# js220_fp_sba.net
KiCad netlist of a schematic drawn in EAGLE
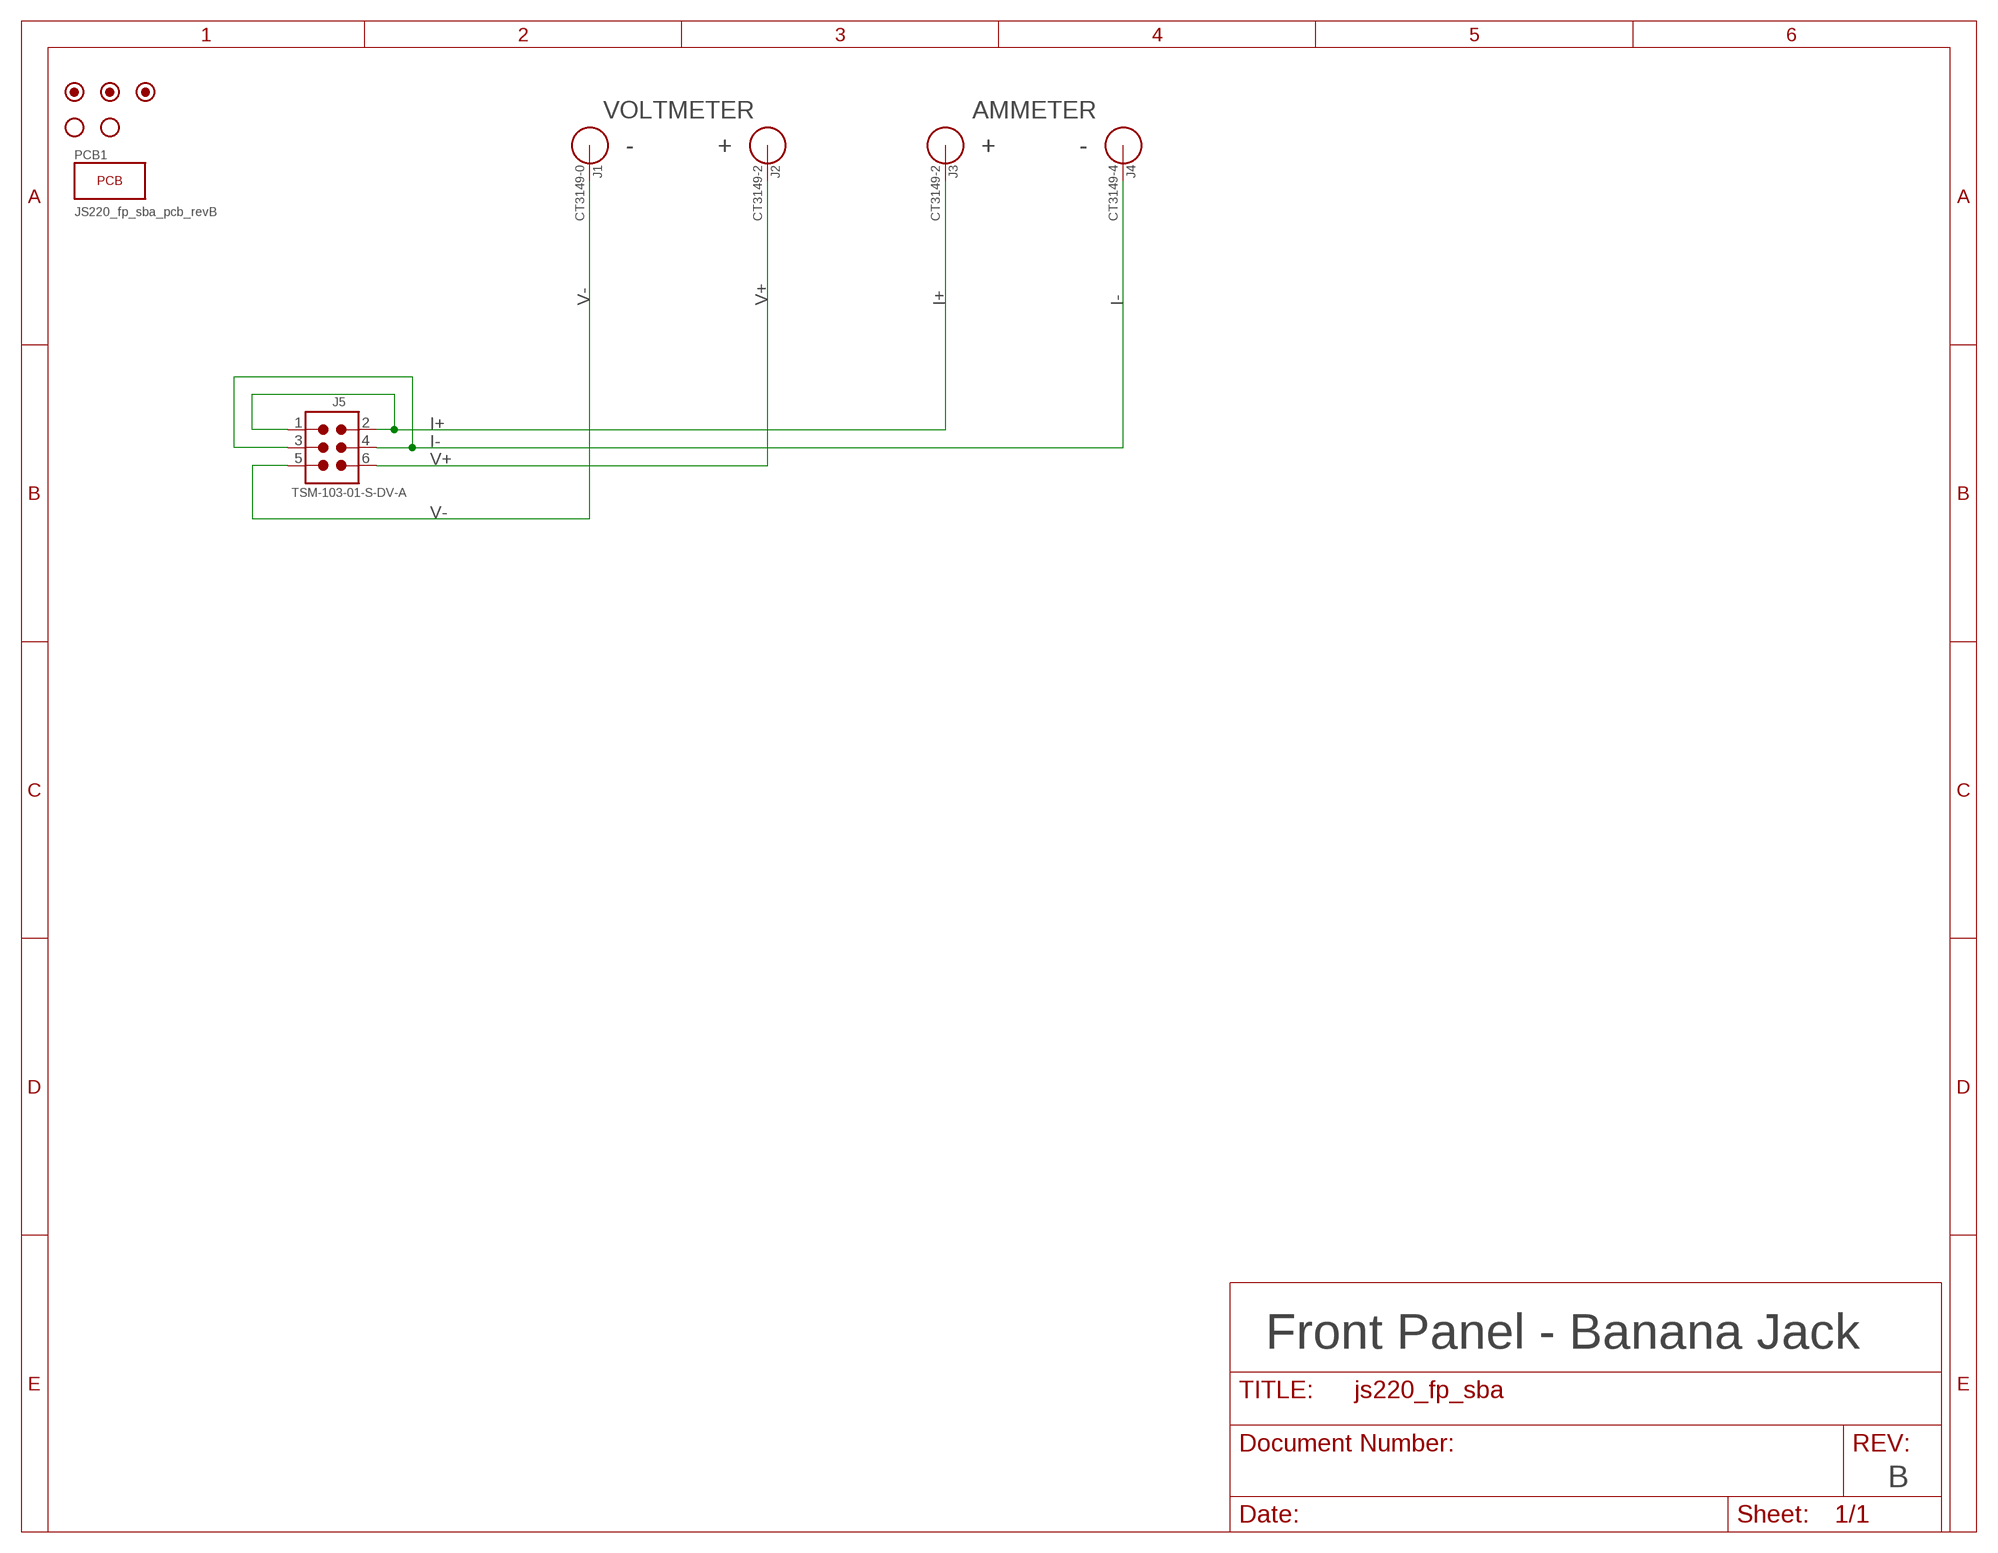
[diagram p0: schematic, sheet 1]

(export (version "E")
  (design (tool "Eeschema 10.0.6"))
  (components
    (comp (ref "FUD1")
      (value "FIDUCIAL_1MM")
      (footprint "eagle-import:FIDUCIAL_1MM_2MM")
      (libsource (lib "eagle-import") (part "FIDUCIAL_1MM"))
    )
    (comp (ref "FUD2")
      (value "FIDUCIAL_1MM")
      (footprint "eagle-import:FIDUCIAL_1MM_2MM")
      (libsource (lib "eagle-import") (part "FIDUCIAL_1MM"))
    )
    (comp (ref "FUD3")
      (value "FIDUCIAL_1MM")
      (footprint "eagle-import:FIDUCIAL_1MM_2MM")
      (libsource (lib "eagle-import") (part "FIDUCIAL_1MM"))
    )
    (comp (ref "H1")
      (value "HOLE_#6_NORESTRICT")
      (footprint "eagle-import:HOLE_3.5MM_NORESTRICT")
      (libsource (lib "eagle-import") (part "HOLE_#6_NORESTRICT"))
    )
    (comp (ref "H2")
      (value "HOLE_#6_NORESTRICT")
      (footprint "eagle-import:HOLE_3.5MM_NORESTRICT")
      (libsource (lib "eagle-import") (part "HOLE_#6_NORESTRICT"))
    )
    (comp (ref "J1")
      (value "CT3149-0")
      (footprint "eagle-import:CT3149")
      (libsource (lib "eagle-import") (part "BANANA-JACK_CT3149"))
    )
    (comp (ref "J2")
      (value "CT3149-2")
      (footprint "eagle-import:CT3149")
      (libsource (lib "eagle-import") (part "BANANA-JACK_CT3149"))
    )
    (comp (ref "J3")
      (value "CT3149-2")
      (footprint "eagle-import:CT3149")
      (libsource (lib "eagle-import") (part "BANANA-JACK_CT3149"))
    )
    (comp (ref "J4")
      (value "CT3149-4")
      (footprint "eagle-import:CT3149")
      (libsource (lib "eagle-import") (part "BANANA-JACK_CT3149"))
    )
    (comp (ref "J5")
      (value "TSM-103-01-S-DV-A")
      (footprint "eagle-import:CONN_0.1_3X2_MSA")
      (libsource (lib "eagle-import") (part "CONN_0.1_3X2_MSA"))
    )
  )
  (nets
    (net (code "1") (name "/I+") (class "Default")
      (node (ref "J3") (pin "A") (pinfunction "1_A") (pintype "bidirectional"))
      (node (ref "J5") (pin "1") (pinfunction "1_1") (pintype "bidirectional"))
      (node (ref "J5") (pin "2") (pinfunction "2_2") (pintype "bidirectional"))
    )
    (net (code "2") (name "/I-") (class "Default")
      (node (ref "J4") (pin "A") (pinfunction "1_A") (pintype "bidirectional"))
      (node (ref "J5") (pin "3") (pinfunction "3_3") (pintype "bidirectional"))
      (node (ref "J5") (pin "4") (pinfunction "4_4") (pintype "bidirectional"))
    )
    (net (code "3") (name "/V+") (class "Default")
      (node (ref "J2") (pin "A") (pinfunction "1_A") (pintype "bidirectional"))
      (node (ref "J5") (pin "6") (pinfunction "6_6") (pintype "bidirectional"))
    )
    (net (code "4") (name "/V-") (class "Default")
      (node (ref "J1") (pin "A") (pinfunction "1_A") (pintype "bidirectional"))
      (node (ref "J5") (pin "5") (pinfunction "5_5") (pintype "bidirectional"))
    )
  )
)
